# SnifferRS232.net
KiCad netlist of a schematic drawn in Altium Designer
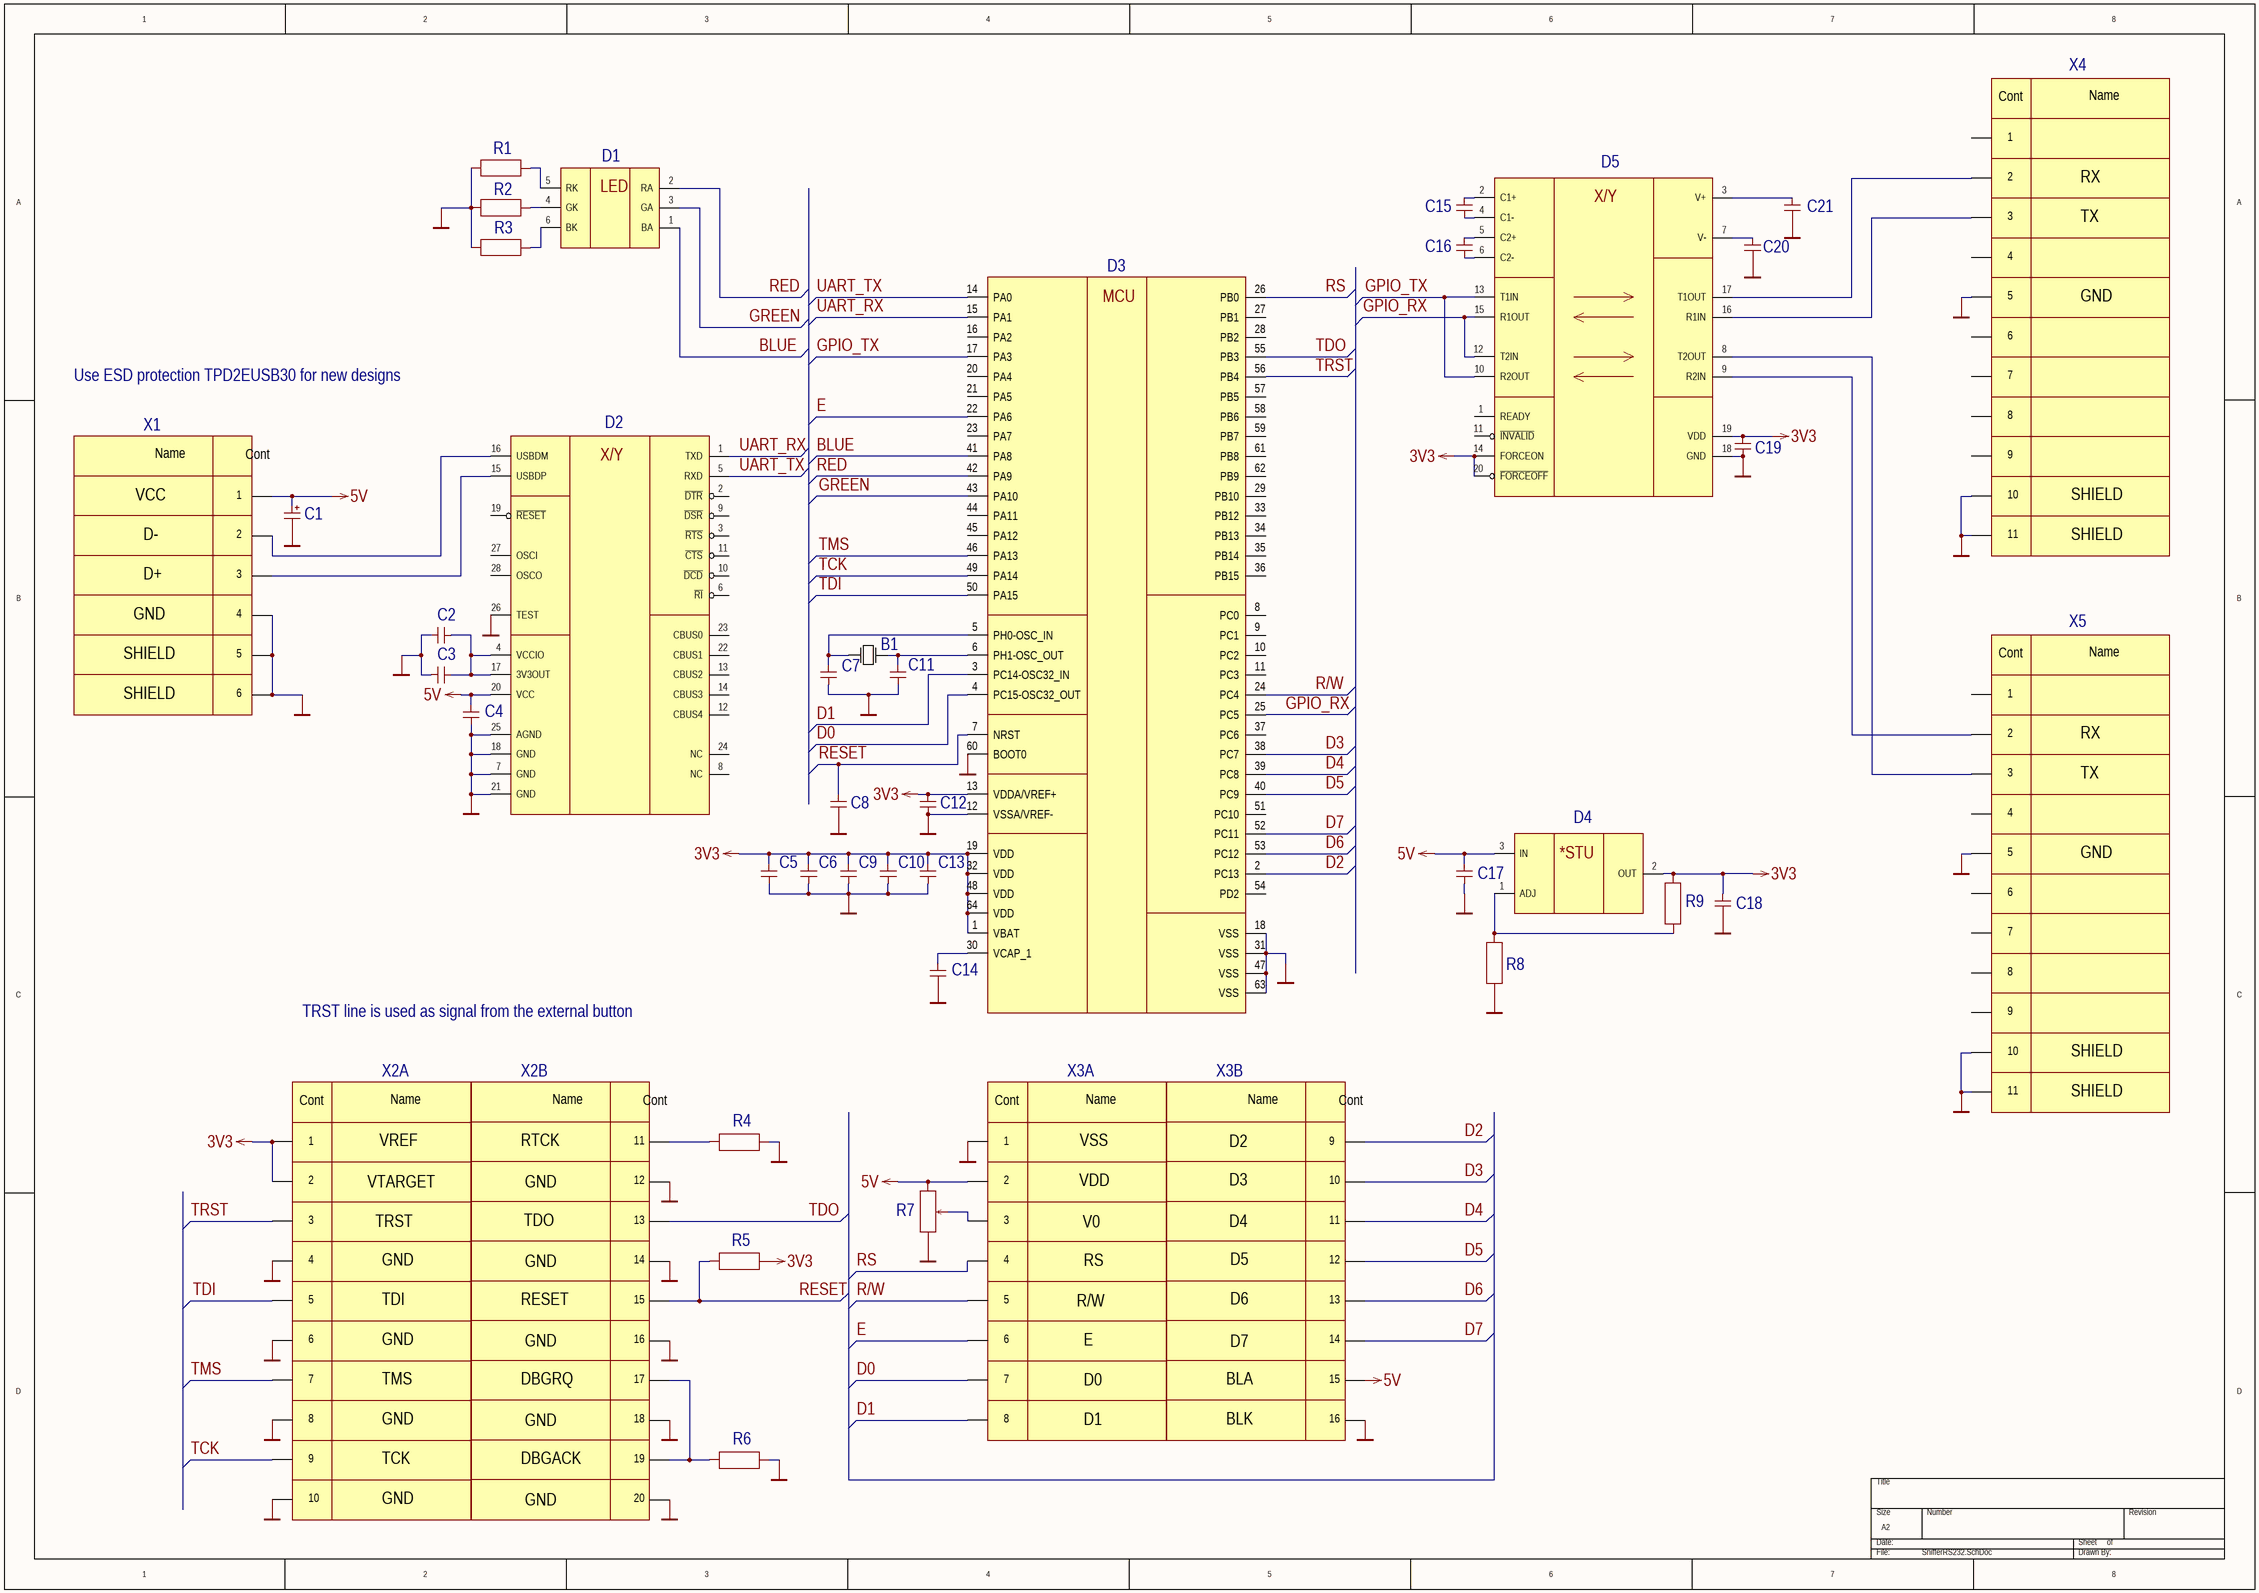
[diagram p0: SnifferRS232.SchDoc]

(export (version "E")
  (design (tool "Eeschema 10.0.6"))
  (components
    (comp (ref "B1")
      (value "ZQ1 KX-3H 25.0 MHz")
      (footprint "KX-3H")
      (description "Crystal oscillator")
      (fields (field (name "MANUFACTURER") "Geyer Electronic"))
      (libsource (lib "Devices") (part "Oscillator"))
    )
    (comp (ref "C1")
      (value "1208-16 V-100uF")
      (footprint "CAP_5x11")
      (description "Electrolytic capacitor")
      (libsource (lib "Passive,Diodes") (part "Cap_el"))
    )
    (comp (ref "C2")
      (value "0805-16 V-X7R-0.1uF±10 %")
      (footprint "SMD-0805C")
      (description "Capacitor")
      (libsource (lib "Passive,Diodes") (part "Cap"))
    )
    (comp (ref "C3")
      (value "0805-16 V-X7R-0.1uF±10 %")
      (footprint "SMD-0805C")
      (description "Capacitor")
      (libsource (lib "Passive,Diodes") (part "Cap"))
    )
    (comp (ref "C4")
      (value "0805-16 V-X7R-0.1uF±10 %")
      (footprint "SMD-0805C")
      (description "Capacitor")
      (libsource (lib "Passive,Diodes") (part "Cap"))
    )
    (comp (ref "C5")
      (value "0805-16 V-X7R-0.1uF±10 %")
      (footprint "SMD-0805C")
      (description "Capacitor")
      (libsource (lib "Passive,Diodes") (part "Cap"))
    )
    (comp (ref "C6")
      (value "0805-16 V-X7R-0.1uF±10 %")
      (footprint "SMD-0805C")
      (description "Capacitor")
      (libsource (lib "Passive,Diodes") (part "Cap"))
    )
    (comp (ref "C7")
      (value "0805-50 V-COG-22pF±5 %")
      (footprint "SMD-0805C")
      (description "Capacitor")
      (libsource (lib "Passive,Diodes") (part "Cap"))
    )
    (comp (ref "C8")
      (value "0805-16 V-X7R-0.1uF±10 %")
      (footprint "SMD-0805C")
      (description "Capacitor")
      (libsource (lib "Passive,Diodes") (part "Cap"))
    )
    (comp (ref "C9")
      (value "0805-16 V-X7R-0.1uF±10 %")
      (footprint "SMD-0805C")
      (description "Capacitor")
      (libsource (lib "Passive,Diodes") (part "Cap"))
    )
    (comp (ref "C10")
      (value "0805-16 V-X7R-0.1uF±10 %")
      (footprint "SMD-0805C")
      (description "Capacitor")
      (libsource (lib "Passive,Diodes") (part "Cap"))
    )
    (comp (ref "C11")
      (value "0805-50 V-COG-22pF±5 %")
      (footprint "SMD-0805C")
      (description "Capacitor")
      (libsource (lib "Passive,Diodes") (part "Cap"))
    )
    (comp (ref "C12")
      (value "0805-16 V-X7R-0.1uF±10 %")
      (footprint "SMD-0805C")
      (description "Capacitor")
      (libsource (lib "Passive,Diodes") (part "Cap"))
    )
    (comp (ref "C13")
      (value "0805-16 V-X7R-0.1uF±10 %")
      (footprint "SMD-0805C")
      (description "Capacitor")
      (libsource (lib "Passive,Diodes") (part "Cap"))
    )
    (comp (ref "C14")
      (value "0805-16 V-X7R-4.7uF±10 %")
      (footprint "SMD-0805C")
      (description "Capacitor")
      (libsource (lib "Passive,Diodes") (part "Cap"))
    )
    (comp (ref "C15")
      (value "0805-16 V-X7R-0.1uF±10 %")
      (footprint "SMD-0805C")
      (description "Capacitor")
      (libsource (lib "Passive,Diodes") (part "Cap"))
    )
    (comp (ref "C16")
      (value "0805-16 V-X7R-0.1uF±10 %")
      (footprint "SMD-0805C")
      (description "Capacitor")
      (libsource (lib "Passive,Diodes") (part "Cap"))
    )
    (comp (ref "C17")
      (value "0805-16 V-X7R-1uF±10 %")
      (footprint "SMD-0805C")
      (description "Capacitor")
      (libsource (lib "Passive,Diodes") (part "Cap"))
    )
    (comp (ref "C18")
      (value "0805-16 V-X7R-1uF±10 %")
      (footprint "SMD-0805C")
      (description "Capacitor")
      (libsource (lib "Passive,Diodes") (part "Cap"))
    )
    (comp (ref "C19")
      (value "0805-16 V-X7R-0.1uF±10 %")
      (footprint "SMD-0805C")
      (description "Capacitor")
      (libsource (lib "Passive,Diodes") (part "Cap"))
    )
    (comp (ref "C20")
      (value "0805-16 V-X7R-0.1uF±10 %")
      (footprint "SMD-0805C")
      (description "Capacitor")
      (libsource (lib "Passive,Diodes") (part "Cap"))
    )
    (comp (ref "C21")
      (value "0805-16 V-X7R-0.1uF±10 %")
      (footprint "SMD-0805C")
      (description "Capacitor")
      (libsource (lib "Passive,Diodes") (part "Cap"))
    )
    (comp (ref "D1")
      (value "TO-5050BC-MRPBFGF")
      (footprint "smd_50x50")
      (description "Surface mount smd LED")
      (fields (field (name "MANUFACTURER") "Oasis Technology"))
      (libsource (lib "Devices") (part "LED_RGB"))
    )
    (comp (ref "D2")
      (value "FT232RL")
      (footprint "SSOP-28_M")
      (description "USB UART Asynchronous Serial Data Transfer Chip, SSOP-28, Tape and Reel")
      (fields (field (name "MANUFACTURER") "FTDI"))
      (libsource (lib "Devices") (part "FT232R"))
    )
    (comp (ref "D3")
      (value "STM32F446RCT6")
      (footprint "LQFP64")
      (fields (field (name "MANUFACTURER") "STMicroelectronics"))
      (libsource (lib "Devices") (part "STM32F446RxT"))
    )
    (comp (ref "D4")
      (value "LM317DCYR")
      (footprint "Devices:SOT223_M")
      (description "3-Terminal Adjustable Regulator")
      (fields (field (name "MANUFACTURER") "Texas Instruments"))
      (libsource (lib "Devices") (part "LM317"))
    )
    (comp (ref "D5")
      (value "MAX3225ECAP+")
      (footprint "TSSOP-20")
      (description "±15kV ESD-Protected, 1µA, 1Mbps, 3.0V to 5.5V,  RS-232 Transceivers with AutoShutdown Plus")
      (fields (field (name "MANUFACTURER") "Maxim Integrated"))
      (libsource (lib "Devices") (part "MAX3225"))
    )
    (comp (ref "R1")
      (value "0805±5 %-680 Ohm")
      (footprint "SMD-0805-RES")
      (description "Resistor")
      (libsource (lib "Passive,Diodes") (part "Res"))
    )
    (comp (ref "R2")
      (value "0805±5 %-680 Ohm")
      (footprint "SMD-0805-RES")
      (description "Resistor")
      (libsource (lib "Passive,Diodes") (part "Res"))
    )
    (comp (ref "R3")
      (value "0805±5 %-0 Ohm")
      (footprint "SMD-0805-RES")
      (description "Resistor")
      (libsource (lib "Passive,Diodes") (part "Res"))
    )
    (comp (ref "R4")
      (value "0805±5 %-10 kOhm")
      (footprint "SMD-0805-RES")
      (description "Resistor")
      (libsource (lib "") (part "Res_1"))
    )
    (comp (ref "R5")
      (value "0805±5 %-10 kOhm")
      (footprint "SMD-0805-RES")
      (description "Resistor")
      (libsource (lib "Passive,Diodes") (part "Res"))
    )
    (comp (ref "R6")
      (value "0805±5 %-10 kOhm")
      (footprint "SMD-0805-RES")
      (description "Resistor")
      (libsource (lib "") (part "Res_1"))
    )
    (comp (ref "R7")
      (value "CA9PV10-10KA2020")
      (footprint "CA9V")
      (description "Potentiometer")
      (fields (field (name "MANUFACTURER") "ACP Technologies"))
      (libsource (lib "Passive,Diodes") (part "Potentiometer"))
    )
    (comp (ref "R8")
      (value "0805±1 %-2 kOhm")
      (footprint "SMD-0805-RES")
      (description "Resistor")
      (libsource (lib "Passive,Diodes") (part "Res"))
    )
    (comp (ref "R9")
      (value "0805±1 %-1.3 kOhm")
      (footprint "SMD-0805-RES")
      (description "Resistor")
      (libsource (lib "") (part "Res_1"))
    )
    (comp (ref "X1")
      (value "DS1099-BN0")
      (footprint "FCI USB 61729-0010BLF")
      (description "USB-B connector")
      (fields (field (name "MANUFACTURER") "Connfly Electronic"))
      (libsource (lib "Connectors") (part "USB-B"))
    )
    (comp (ref "X2")
      (value "DS1021-2*10SF11-B")
      (footprint "PLD2x10")
      (description "PLD-20 connector")
      (fields (field (name "MANUFACTURER") "Connfly Electronic"))
      (libsource (lib "Connectors") (part "PLD2x10"))
    )
    (comp (ref "X3")
      (value "DS1021-1*16SF112")
      (footprint "PLS-16_12")
      (description "PLD-16 connector")
      (fields (field (name "MANUFACTURER") "Connfly  Electronic"))
      (libsource (lib "") (part "PLD2x8_1"))
    )
    (comp (ref "X4")
      (value "DS1037-09FNAKT74-0CC")
      (footprint "DB-9F")
      (description "DB-9 female connector")
      (fields (field (name "MANUFACTURER") "Connfly Electronic"))
      (libsource (lib "Connectors") (part "DB-9"))
    )
    (comp (ref "X5")
      (value "DS1037-09MNAKT74-0CC")
      (footprint "DB-9M")
      (description "DB-9 male connector")
      (fields (field (name "MANUFACTURER") "Connfly Electronic"))
      (libsource (lib "Connectors") (part "DB-9"))
    )
  )
  (nets
    (net (code "1") (name "/BLUE") (class "Default")
      (node (ref "D1") (pin "1") (pinfunction "BA_1") (pintype "passive"))
      (node (ref "D3") (pin "41") (pinfunction "PA8_41") (pintype "passive"))
    )
    (net (code "2") (name "/D0") (class "Default")
      (node (ref "D3") (pin "4") (pinfunction "PC15-OSC32_OUT_4") (pintype "passive"))
      (node (ref "X3") (pin "7") (pinfunction "7_7") (pintype "passive"))
    )
    (net (code "3") (name "/D1") (class "Default")
      (node (ref "D3") (pin "3") (pinfunction "PC14-OSC32_IN_3") (pintype "passive"))
      (node (ref "X3") (pin "8") (pinfunction "8_8") (pintype "passive"))
    )
    (net (code "4") (name "/D2") (class "Default")
      (node (ref "D3") (pin "2") (pinfunction "PC13_2") (pintype "passive"))
      (node (ref "X3") (pin "9") (pinfunction "9_9") (pintype "passive"))
    )
    (net (code "5") (name "/D3") (class "Default")
      (node (ref "D3") (pin "38") (pinfunction "PC7_38") (pintype "passive"))
      (node (ref "X3") (pin "10") (pinfunction "10_10") (pintype "passive"))
    )
    (net (code "6") (name "/D4") (class "Default")
      (node (ref "D3") (pin "39") (pinfunction "PC8_39") (pintype "passive"))
      (node (ref "X3") (pin "11") (pinfunction "11_11") (pintype "passive"))
    )
    (net (code "7") (name "/D5") (class "Default")
      (node (ref "D3") (pin "40") (pinfunction "PC9_40") (pintype "passive"))
      (node (ref "X3") (pin "12") (pinfunction "12_12") (pintype "passive"))
    )
    (net (code "8") (name "/D6") (class "Default")
      (node (ref "D3") (pin "53") (pinfunction "PC12_53") (pintype "passive"))
      (node (ref "X3") (pin "13") (pinfunction "13_13") (pintype "passive"))
    )
    (net (code "9") (name "/D7") (class "Default")
      (node (ref "D3") (pin "52") (pinfunction "PC11_52") (pintype "passive"))
      (node (ref "X3") (pin "14") (pinfunction "14_14") (pintype "passive"))
    )
    (net (code "10") (name "/E") (class "Default")
      (node (ref "D3") (pin "22") (pinfunction "PA6_22") (pintype "passive"))
      (node (ref "X3") (pin "6") (pinfunction "6_6") (pintype "passive"))
    )
    (net (code "11") (name "/GPIO_RX") (class "Default")
      (node (ref "D3") (pin "25") (pinfunction "PC5_25") (pintype "passive"))
      (node (ref "D5") (pin "12") (pinfunction "T2IN_12") (pintype "passive"))
      (node (ref "D5") (pin "15") (pinfunction "R1OUT_15") (pintype "passive"))
    )
    (net (code "12") (name "/GPIO_TX") (class "Default")
      (node (ref "D3") (pin "17") (pinfunction "PA3_17") (pintype "passive"))
      (node (ref "D5") (pin "10") (pinfunction "R2OUT_10") (pintype "passive"))
      (node (ref "D5") (pin "13") (pinfunction "T1IN_13") (pintype "passive"))
    )
    (net (code "13") (name "/GREEN") (class "Default")
      (node (ref "D1") (pin "3") (pinfunction "GA_3") (pintype "passive"))
      (node (ref "D3") (pin "43") (pinfunction "PA10_43") (pintype "passive"))
    )
    (net (code "14") (name "/RED") (class "Default")
      (node (ref "D1") (pin "2") (pinfunction "RA_2") (pintype "passive"))
      (node (ref "D3") (pin "42") (pinfunction "PA9_42") (pintype "passive"))
    )
    (net (code "15") (name "/RESET") (class "Default")
      (node (ref "C8") (pin "1") (pinfunction "1_1") (pintype "passive"))
      (node (ref "D3") (pin "7") (pinfunction "NRST_7") (pintype "passive"))
      (node (ref "R5") (pin "2") (pinfunction "2_2") (pintype "passive"))
      (node (ref "X2") (pin "15") (pinfunction "15_15") (pintype "passive"))
    )
    (net (code "16") (name "/RS") (class "Default")
      (node (ref "D3") (pin "26") (pinfunction "PB0_26") (pintype "passive"))
      (node (ref "X3") (pin "4") (pinfunction "4_4") (pintype "passive"))
    )
    (net (code "17") (name "/R{slash}W") (class "Default")
      (node (ref "D3") (pin "24") (pinfunction "PC4_24") (pintype "passive"))
      (node (ref "X3") (pin "5") (pinfunction "5_5") (pintype "passive"))
    )
    (net (code "18") (name "/TCK") (class "Default")
      (node (ref "D3") (pin "49") (pinfunction "PA14_49") (pintype "passive"))
      (node (ref "X2") (pin "9") (pinfunction "9_9") (pintype "passive"))
    )
    (net (code "19") (name "/TDI") (class "Default")
      (node (ref "D3") (pin "50") (pinfunction "PA15_50") (pintype "passive"))
      (node (ref "X2") (pin "5") (pinfunction "5_5") (pintype "passive"))
    )
    (net (code "20") (name "/TDO") (class "Default")
      (node (ref "D3") (pin "55") (pinfunction "PB3_55") (pintype "passive"))
      (node (ref "X2") (pin "13") (pinfunction "13_13") (pintype "passive"))
    )
    (net (code "21") (name "/TMS") (class "Default")
      (node (ref "D3") (pin "46") (pinfunction "PA13_46") (pintype "passive"))
      (node (ref "X2") (pin "7") (pinfunction "7_7") (pintype "passive"))
    )
    (net (code "22") (name "/TRST") (class "Default")
      (node (ref "D3") (pin "56") (pinfunction "PB4_56") (pintype "passive"))
      (node (ref "X2") (pin "3") (pinfunction "3_3") (pintype "passive"))
    )
    (net (code "23") (name "/UART_RX") (class "Default")
      (node (ref "D2") (pin "1") (pinfunction "TXD_1") (pintype "passive"))
      (node (ref "D3") (pin "15") (pinfunction "PA1_15") (pintype "passive"))
    )
    (net (code "24") (name "/UART_TX") (class "Default")
      (node (ref "D2") (pin "5") (pinfunction "RXD_5") (pintype "passive"))
      (node (ref "D3") (pin "14") (pinfunction "PA0_14") (pintype "passive"))
    )
    (net (code "25") (name "3V3") (class "Default")
      (node (ref "C10") (pin "1") (pinfunction "1_1") (pintype "passive"))
      (node (ref "C12") (pin "1") (pinfunction "1_1") (pintype "passive"))
      (node (ref "C13") (pin "1") (pinfunction "1_1") (pintype "passive"))
      (node (ref "C18") (pin "2") (pinfunction "2_2") (pintype "passive"))
      (node (ref "C19") (pin "1") (pinfunction "1_1") (pintype "passive"))
      (node (ref "C5") (pin "1") (pinfunction "1_1") (pintype "passive"))
      (node (ref "C6") (pin "1") (pinfunction "1_1") (pintype "passive"))
      (node (ref "C9") (pin "1") (pinfunction "1_1") (pintype "passive"))
      (node (ref "D3") (pin "1") (pinfunction "VBAT_1") (pintype "power_in"))
      (node (ref "D3") (pin "13") (pinfunction "VDDA/VREF+_13") (pintype "power_in"))
      (node (ref "D3") (pin "19") (pinfunction "VDD_19") (pintype "power_in"))
      (node (ref "D3") (pin "32") (pinfunction "VDD_32") (pintype "power_in"))
      (node (ref "D3") (pin "48") (pinfunction "VDD_48") (pintype "power_in"))
      (node (ref "D3") (pin "64") (pinfunction "VDD_64") (pintype "power_in"))
      (node (ref "D4") (pin "2") (pinfunction "OUT_2") (pintype "power_in"))
      (node (ref "D5") (pin "14") (pinfunction "FORCEON_14") (pintype "passive"))
      (node (ref "D5") (pin "19") (pinfunction "VDD_19") (pintype "power_in"))
      (node (ref "D5") (pin "20") (pinfunction "~{FORCEOFF}_20") (pintype "passive"))
      (node (ref "R5") (pin "1") (pinfunction "1_1") (pintype "passive"))
      (node (ref "R9") (pin "2") (pinfunction "2_2") (pintype "passive"))
      (node (ref "X2") (pin "1") (pinfunction "1_1") (pintype "passive"))
      (node (ref "X2") (pin "2") (pinfunction "2_2") (pintype "passive"))
    )
    (net (code "26") (name "5V") (class "Default")
      (node (ref "C1") (pin "1") (pinfunction "1_1") (pintype "passive"))
      (node (ref "C17") (pin "2") (pinfunction "2_2") (pintype "passive"))
      (node (ref "C4") (pin "1") (pinfunction "1_1") (pintype "passive"))
      (node (ref "D2") (pin "20") (pinfunction "VCC_20") (pintype "power_in"))
      (node (ref "D4") (pin "3") (pinfunction "IN_3") (pintype "power_in"))
      (node (ref "R7") (pin "3") (pinfunction "3_3") (pintype "passive"))
      (node (ref "X1") (pin "1") (pinfunction "1_1") (pintype "passive"))
      (node (ref "X3") (pin "15") (pinfunction "15_15") (pintype "passive"))
      (node (ref "X3") (pin "2") (pinfunction "2_2") (pintype "passive"))
    )
    (net (code "27") (name "GND") (class "Default")
      (node (ref "C1") (pin "2") (pinfunction "2_2") (pintype "passive"))
      (node (ref "C10") (pin "2") (pinfunction "2_2") (pintype "passive"))
      (node (ref "C11") (pin "2") (pinfunction "2_2") (pintype "passive"))
      (node (ref "C12") (pin "2") (pinfunction "2_2") (pintype "passive"))
      (node (ref "C13") (pin "2") (pinfunction "2_2") (pintype "passive"))
      (node (ref "C14") (pin "2") (pinfunction "2_2") (pintype "passive"))
      (node (ref "C17") (pin "1") (pinfunction "1_1") (pintype "passive"))
      (node (ref "C18") (pin "1") (pinfunction "1_1") (pintype "passive"))
      (node (ref "C19") (pin "2") (pinfunction "2_2") (pintype "passive"))
      (node (ref "C2") (pin "1") (pinfunction "1_1") (pintype "passive"))
      (node (ref "C20") (pin "2") (pinfunction "2_2") (pintype "passive"))
      (node (ref "C21") (pin "2") (pinfunction "2_2") (pintype "passive"))
      (node (ref "C3") (pin "1") (pinfunction "1_1") (pintype "passive"))
      (node (ref "C4") (pin "2") (pinfunction "2_2") (pintype "passive"))
      (node (ref "C5") (pin "2") (pinfunction "2_2") (pintype "passive"))
      (node (ref "C6") (pin "2") (pinfunction "2_2") (pintype "passive"))
      (node (ref "C7") (pin "2") (pinfunction "2_2") (pintype "passive"))
      (node (ref "C8") (pin "2") (pinfunction "2_2") (pintype "passive"))
      (node (ref "C9") (pin "2") (pinfunction "2_2") (pintype "passive"))
      (node (ref "D2") (pin "18") (pinfunction "GND_18") (pintype "power_in"))
      (node (ref "D2") (pin "21") (pinfunction "GND_21") (pintype "power_in"))
      (node (ref "D2") (pin "25") (pinfunction "AGND_25") (pintype "power_in"))
      (node (ref "D2") (pin "26") (pinfunction "TEST_26") (pintype "passive"))
      (node (ref "D2") (pin "7") (pinfunction "GND_7") (pintype "power_in"))
      (node (ref "D3") (pin "12") (pinfunction "VSSA/VREF-_12") (pintype "power_in"))
      (node (ref "D3") (pin "18") (pinfunction "VSS_18") (pintype "power_in"))
      (node (ref "D3") (pin "31") (pinfunction "VSS_31") (pintype "power_in"))
      (node (ref "D3") (pin "47") (pinfunction "VSS_47") (pintype "power_in"))
      (node (ref "D3") (pin "60") (pinfunction "BOOT0_60") (pintype "passive"))
      (node (ref "D3") (pin "63") (pinfunction "VSS_63") (pintype "power_in"))
      (node (ref "D5") (pin "18") (pinfunction "GND_18") (pintype "power_in"))
      (node (ref "R1") (pin "2") (pinfunction "2_2") (pintype "passive"))
      (node (ref "R2") (pin "2") (pinfunction "2_2") (pintype "passive"))
      (node (ref "R3") (pin "2") (pinfunction "2_2") (pintype "passive"))
      (node (ref "R4") (pin "2") (pinfunction "2_2") (pintype "passive"))
      (node (ref "R6") (pin "2") (pinfunction "2_2") (pintype "passive"))
      (node (ref "R7") (pin "1") (pinfunction "1_1") (pintype "passive"))
      (node (ref "R8") (pin "2") (pinfunction "2_2") (pintype "passive"))
      (node (ref "X1") (pin "4") (pinfunction "4_4") (pintype "passive"))
      (node (ref "X1") (pin "5") (pinfunction "5_5") (pintype "passive"))
      (node (ref "X1") (pin "6") (pinfunction "6_6") (pintype "passive"))
      (node (ref "X2") (pin "10") (pinfunction "10_10") (pintype "passive"))
      (node (ref "X2") (pin "12") (pinfunction "12_12") (pintype "passive"))
      (node (ref "X2") (pin "14") (pinfunction "14_14") (pintype "passive"))
      (node (ref "X2") (pin "16") (pinfunction "16_16") (pintype "passive"))
      (node (ref "X2") (pin "18") (pinfunction "18_18") (pintype "passive"))
      (node (ref "X2") (pin "20") (pinfunction "20_20") (pintype "passive"))
      (node (ref "X2") (pin "4") (pinfunction "4_4") (pintype "passive"))
      (node (ref "X2") (pin "6") (pinfunction "6_6") (pintype "passive"))
      (node (ref "X2") (pin "8") (pinfunction "8_8") (pintype "passive"))
      (node (ref "X3") (pin "1") (pinfunction "1_1") (pintype "passive"))
      (node (ref "X3") (pin "16") (pinfunction "16_16") (pintype "passive"))
      (node (ref "X4") (pin "10") (pinfunction "10_10") (pintype "passive"))
      (node (ref "X4") (pin "11") (pinfunction "11_11") (pintype "passive"))
      (node (ref "X4") (pin "5") (pinfunction "5_5") (pintype "passive"))
      (node (ref "X5") (pin "10") (pinfunction "10_10") (pintype "passive"))
      (node (ref "X5") (pin "11") (pinfunction "11_11") (pintype "passive"))
      (node (ref "X5") (pin "5") (pinfunction "5_5") (pintype "passive"))
    )
    (net (code "28") (name "Net-(B1-OSCIN)") (class "Default")
      (node (ref "B1") (pin "1") (pinfunction "OSCIN_1") (pintype "passive"))
      (node (ref "C11") (pin "1") (pinfunction "1_1") (pintype "passive"))
      (node (ref "D3") (pin "6") (pinfunction "PH1-OSC_OUT_6") (pintype "passive"))
    )
    (net (code "29") (name "Net-(B1-OSCOUT)") (class "Default")
      (node (ref "B1") (pin "2") (pinfunction "OSCOUT_2") (pintype "passive"))
      (node (ref "C7") (pin "1") (pinfunction "1_1") (pintype "passive"))
      (node (ref "D3") (pin "5") (pinfunction "PH0-OSC_IN_5") (pintype "passive"))
    )
    (net (code "30") (name "Net-(D1-BK)") (class "Default")
      (node (ref "D1") (pin "6") (pinfunction "BK_6") (pintype "passive"))
      (node (ref "R3") (pin "1") (pinfunction "1_1") (pintype "passive"))
    )
    (net (code "31") (name "Net-(D1-GK)") (class "Default")
      (node (ref "D1") (pin "4") (pinfunction "GK_4") (pintype "passive"))
      (node (ref "R2") (pin "1") (pinfunction "1_1") (pintype "passive"))
    )
    (net (code "32") (name "Net-(D1-RK)") (class "Default")
      (node (ref "D1") (pin "5") (pinfunction "RK_5") (pintype "passive"))
      (node (ref "R1") (pin "1") (pinfunction "1_1") (pintype "passive"))
    )
    (net (code "33") (name "Net-(D2-3V3OUT)") (class "Default")
      (node (ref "C2") (pin "2") (pinfunction "2_2") (pintype "passive"))
      (node (ref "C3") (pin "2") (pinfunction "2_2") (pintype "passive"))
      (node (ref "D2") (pin "17") (pinfunction "3V3OUT_17") (pintype "power_in"))
      (node (ref "D2") (pin "4") (pinfunction "VCCIO_4") (pintype "power_in"))
    )
    (net (code "34") (name "Net-(D2-USBDM)") (class "Default")
      (node (ref "D2") (pin "16") (pinfunction "USBDM_16") (pintype "passive"))
      (node (ref "X1") (pin "2") (pinfunction "2_2") (pintype "passive"))
    )
    (net (code "35") (name "Net-(D2-USBDP)") (class "Default")
      (node (ref "D2") (pin "15") (pinfunction "USBDP_15") (pintype "passive"))
      (node (ref "X1") (pin "3") (pinfunction "3_3") (pintype "passive"))
    )
    (net (code "36") (name "Net-(D3-VCAP_1)") (class "Default")
      (node (ref "C14") (pin "1") (pinfunction "1_1") (pintype "passive"))
      (node (ref "D3") (pin "30") (pinfunction "VCAP_1_30") (pintype "passive"))
    )
    (net (code "37") (name "Net-(D4-ADJ)") (class "Default")
      (node (ref "D4") (pin "1") (pinfunction "ADJ_1") (pintype "passive"))
      (node (ref "R8") (pin "1") (pinfunction "1_1") (pintype "passive"))
      (node (ref "R9") (pin "1") (pinfunction "1_1") (pintype "passive"))
    )
    (net (code "38") (name "Net-(D5-C1+)") (class "Default")
      (node (ref "C15") (pin "1") (pinfunction "1_1") (pintype "passive"))
      (node (ref "D5") (pin "2") (pinfunction "C1+_2") (pintype "passive"))
    )
    (net (code "39") (name "Net-(D5-C1-)") (class "Default")
      (node (ref "C15") (pin "2") (pinfunction "2_2") (pintype "passive"))
      (node (ref "D5") (pin "4") (pinfunction "C1-_4") (pintype "passive"))
    )
    (net (code "40") (name "Net-(D5-C2+)") (class "Default")
      (node (ref "C16") (pin "1") (pinfunction "1_1") (pintype "passive"))
      (node (ref "D5") (pin "5") (pinfunction "C2+_5") (pintype "passive"))
    )
    (net (code "41") (name "Net-(D5-C2-)") (class "Default")
      (node (ref "C16") (pin "2") (pinfunction "2_2") (pintype "passive"))
      (node (ref "D5") (pin "6") (pinfunction "C2-_6") (pintype "passive"))
    )
    (net (code "42") (name "Net-(D5-R1IN)") (class "Default")
      (node (ref "D5") (pin "16") (pinfunction "R1IN_16") (pintype "passive"))
      (node (ref "X4") (pin "3") (pinfunction "3_3") (pintype "passive"))
    )
    (net (code "43") (name "Net-(D5-R2IN)") (class "Default")
      (node (ref "D5") (pin "9") (pinfunction "R2IN_9") (pintype "passive"))
      (node (ref "X5") (pin "2") (pinfunction "2_2") (pintype "passive"))
    )
    (net (code "44") (name "Net-(D5-T1OUT)") (class "Default")
      (node (ref "D5") (pin "17") (pinfunction "T1OUT_17") (pintype "passive"))
      (node (ref "X4") (pin "2") (pinfunction "2_2") (pintype "passive"))
    )
    (net (code "45") (name "Net-(D5-T2OUT)") (class "Default")
      (node (ref "D5") (pin "8") (pinfunction "T2OUT_8") (pintype "passive"))
      (node (ref "X5") (pin "3") (pinfunction "3_3") (pintype "passive"))
    )
    (net (code "46") (name "Net-(D5-V+)") (class "Default")
      (node (ref "C21") (pin "1") (pinfunction "1_1") (pintype "passive"))
      (node (ref "D5") (pin "3") (pinfunction "V+_3") (pintype "power_in"))
    )
    (net (code "47") (name "Net-(D5-V-)") (class "Default")
      (node (ref "C20") (pin "1") (pinfunction "1_1") (pintype "passive"))
      (node (ref "D5") (pin "7") (pinfunction "V-_7") (pintype "power_in"))
    )
    (net (code "48") (name "Net-(R4-Pad1)") (class "Default")
      (node (ref "R4") (pin "1") (pinfunction "1_1") (pintype "passive"))
      (node (ref "X2") (pin "11") (pinfunction "11_11") (pintype "passive"))
    )
    (net (code "49") (name "Net-(R6-Pad1)") (class "Default")
      (node (ref "R6") (pin "1") (pinfunction "1_1") (pintype "passive"))
      (node (ref "X2") (pin "17") (pinfunction "17_17") (pintype "passive"))
      (node (ref "X2") (pin "19") (pinfunction "19_19") (pintype "passive"))
    )
    (net (code "50") (name "Net-(R7-Pad2)") (class "Default")
      (node (ref "R7") (pin "2") (pinfunction "2_2") (pintype "passive"))
      (node (ref "X3") (pin "3") (pinfunction "3_3") (pintype "passive"))
    )
    (net (code "51") (name "unconnected-(D2-CBUS0-Pad23)") (class "Default")
      (node (ref "D2") (pin "23") (pinfunction "CBUS0_23") (pintype "passive"))
    )
    (net (code "52") (name "unconnected-(D2-CBUS1-Pad22)") (class "Default")
      (node (ref "D2") (pin "22") (pinfunction "CBUS1_22") (pintype "passive"))
    )
    (net (code "53") (name "unconnected-(D2-CBUS2-Pad13)") (class "Default")
      (node (ref "D2") (pin "13") (pinfunction "CBUS2_13") (pintype "passive"))
    )
    (net (code "54") (name "unconnected-(D2-CBUS3-Pad14)") (class "Default")
      (node (ref "D2") (pin "14") (pinfunction "CBUS3_14") (pintype "passive"))
    )
    (net (code "55") (name "unconnected-(D2-CBUS4-Pad12)") (class "Default")
      (node (ref "D2") (pin "12") (pinfunction "CBUS4_12") (pintype "passive"))
    )
    (net (code "56") (name "unconnected-(D2-NC-Pad8)") (class "Default")
      (node (ref "D2") (pin "8") (pinfunction "NC_8") (pintype "passive"))
    )
    (net (code "57") (name "unconnected-(D2-NC-Pad24)") (class "Default")
      (node (ref "D2") (pin "24") (pinfunction "NC_24") (pintype "passive"))
    )
    (net (code "58") (name "unconnected-(D2-OSCI-Pad27)") (class "Default")
      (node (ref "D2") (pin "27") (pinfunction "OSCI_27") (pintype "passive"))
    )
    (net (code "59") (name "unconnected-(D2-OSCO-Pad28)") (class "Default")
      (node (ref "D2") (pin "28") (pinfunction "OSCO_28") (pintype "passive"))
    )
    (net (code "60") (name "unconnected-(D2-~{CTS}-Pad11)") (class "Default")
      (node (ref "D2") (pin "11") (pinfunction "~{CTS}_11") (pintype "passive"))
    )
    (net (code "61") (name "unconnected-(D2-~{DCD}-Pad10)") (class "Default")
      (node (ref "D2") (pin "10") (pinfunction "~{DCD}_10") (pintype "passive"))
    )
    (net (code "62") (name "unconnected-(D2-~{DSR}-Pad9)") (class "Default")
      (node (ref "D2") (pin "9") (pinfunction "~{DSR}_9") (pintype "passive"))
    )
    (net (code "63") (name "unconnected-(D2-~{DTR}-Pad2)") (class "Default")
      (node (ref "D2") (pin "2") (pinfunction "~{DTR}_2") (pintype "passive"))
    )
    (net (code "64") (name "unconnected-(D2-~{RESET}-Pad19)") (class "Default")
      (node (ref "D2") (pin "19") (pinfunction "~{RESET}_19") (pintype "passive"))
    )
    (net (code "65") (name "unconnected-(D2-~{RI}-Pad6)") (class "Default")
      (node (ref "D2") (pin "6") (pinfunction "~{RI}_6") (pintype "passive"))
    )
    (net (code "66") (name "unconnected-(D2-~{RTS}-Pad3)") (class "Default")
      (node (ref "D2") (pin "3") (pinfunction "~{RTS}_3") (pintype "passive"))
    )
    (net (code "67") (name "unconnected-(D3-PA2-Pad16)") (class "Default")
      (node (ref "D3") (pin "16") (pinfunction "PA2_16") (pintype "passive"))
    )
    (net (code "68") (name "unconnected-(D3-PA4-Pad20)") (class "Default")
      (node (ref "D3") (pin "20") (pinfunction "PA4_20") (pintype "passive"))
    )
    (net (code "69") (name "unconnected-(D3-PA5-Pad21)") (class "Default")
      (node (ref "D3") (pin "21") (pinfunction "PA5_21") (pintype "passive"))
    )
    (net (code "70") (name "unconnected-(D3-PA7-Pad23)") (class "Default")
      (node (ref "D3") (pin "23") (pinfunction "PA7_23") (pintype "passive"))
    )
    (net (code "71") (name "unconnected-(D3-PA11-Pad44)") (class "Default")
      (node (ref "D3") (pin "44") (pinfunction "PA11_44") (pintype "passive"))
    )
    (net (code "72") (name "unconnected-(D3-PA12-Pad45)") (class "Default")
      (node (ref "D3") (pin "45") (pinfunction "PA12_45") (pintype "passive"))
    )
    (net (code "73") (name "unconnected-(D3-PB1-Pad27)") (class "Default")
      (node (ref "D3") (pin "27") (pinfunction "PB1_27") (pintype "passive"))
    )
    (net (code "74") (name "unconnected-(D3-PB2-Pad28)") (class "Default")
      (node (ref "D3") (pin "28") (pinfunction "PB2_28") (pintype "passive"))
    )
    (net (code "75") (name "unconnected-(D3-PB5-Pad57)") (class "Default")
      (node (ref "D3") (pin "57") (pinfunction "PB5_57") (pintype "passive"))
    )
    (net (code "76") (name "unconnected-(D3-PB6-Pad58)") (class "Default")
      (node (ref "D3") (pin "58") (pinfunction "PB6_58") (pintype "passive"))
    )
    (net (code "77") (name "unconnected-(D3-PB7-Pad59)") (class "Default")
      (node (ref "D3") (pin "59") (pinfunction "PB7_59") (pintype "passive"))
    )
    (net (code "78") (name "unconnected-(D3-PB8-Pad61)") (class "Default")
      (node (ref "D3") (pin "61") (pinfunction "PB8_61") (pintype "passive"))
    )
    (net (code "79") (name "unconnected-(D3-PB9-Pad62)") (class "Default")
      (node (ref "D3") (pin "62") (pinfunction "PB9_62") (pintype "passive"))
    )
    (net (code "80") (name "unconnected-(D3-PB10-Pad29)") (class "Default")
      (node (ref "D3") (pin "29") (pinfunction "PB10_29") (pintype "passive"))
    )
    (net (code "81") (name "unconnected-(D3-PB12-Pad33)") (class "Default")
      (node (ref "D3") (pin "33") (pinfunction "PB12_33") (pintype "passive"))
    )
    (net (code "82") (name "unconnected-(D3-PB13-Pad34)") (class "Default")
      (node (ref "D3") (pin "34") (pinfunction "PB13_34") (pintype "passive"))
    )
    (net (code "83") (name "unconnected-(D3-PB14-Pad35)") (class "Default")
      (node (ref "D3") (pin "35") (pinfunction "PB14_35") (pintype "passive"))
    )
    (net (code "84") (name "unconnected-(D3-PB15-Pad36)") (class "Default")
      (node (ref "D3") (pin "36") (pinfunction "PB15_36") (pintype "passive"))
    )
    (net (code "85") (name "unconnected-(D3-PC0-Pad8)") (class "Default")
      (node (ref "D3") (pin "8") (pinfunction "PC0_8") (pintype "passive"))
    )
    (net (code "86") (name "unconnected-(D3-PC1-Pad9)") (class "Default")
      (node (ref "D3") (pin "9") (pinfunction "PC1_9") (pintype "passive"))
    )
    (net (code "87") (name "unconnected-(D3-PC2-Pad10)") (class "Default")
      (node (ref "D3") (pin "10") (pinfunction "PC2_10") (pintype "passive"))
    )
    (net (code "88") (name "unconnected-(D3-PC3-Pad11)") (class "Default")
      (node (ref "D3") (pin "11") (pinfunction "PC3_11") (pintype "passive"))
    )
    (net (code "89") (name "unconnected-(D3-PC6-Pad37)") (class "Default")
      (node (ref "D3") (pin "37") (pinfunction "PC6_37") (pintype "passive"))
    )
    (net (code "90") (name "unconnected-(D3-PC10-Pad51)") (class "Default")
      (node (ref "D3") (pin "51") (pinfunction "PC10_51") (pintype "passive"))
    )
    (net (code "91") (name "unconnected-(D3-PD2-Pad54)") (class "Default")
      (node (ref "D3") (pin "54") (pinfunction "PD2_54") (pintype "passive"))
    )
    (net (code "92") (name "unconnected-(D5-READY-Pad1)") (class "Default")
      (node (ref "D5") (pin "1") (pinfunction "READY_1") (pintype "passive"))
    )
    (net (code "93") (name "unconnected-(D5-~{INVALID}-Pad11)") (class "Default")
      (node (ref "D5") (pin "11") (pinfunction "~{INVALID}_11") (pintype "passive"))
    )
    (net (code "94") (name "unconnected-(X4-Pad1)") (class "Default")
      (node (ref "X4") (pin "1") (pinfunction "1_1") (pintype "passive"))
    )
    (net (code "95") (name "unconnected-(X4-Pad4)") (class "Default")
      (node (ref "X4") (pin "4") (pinfunction "4_4") (pintype "passive"))
    )
    (net (code "96") (name "unconnected-(X4-Pad6)") (class "Default")
      (node (ref "X4") (pin "6") (pinfunction "6_6") (pintype "passive"))
    )
    (net (code "97") (name "unconnected-(X4-Pad7)") (class "Default")
      (node (ref "X4") (pin "7") (pinfunction "7_7") (pintype "passive"))
    )
    (net (code "98") (name "unconnected-(X4-Pad8)") (class "Default")
      (node (ref "X4") (pin "8") (pinfunction "8_8") (pintype "passive"))
    )
    (net (code "99") (name "unconnected-(X4-Pad9)") (class "Default")
      (node (ref "X4") (pin "9") (pinfunction "9_9") (pintype "passive"))
    )
    (net (code "100") (name "unconnected-(X5-Pad1)") (class "Default")
      (node (ref "X5") (pin "1") (pinfunction "1_1") (pintype "passive"))
    )
    (net (code "101") (name "unconnected-(X5-Pad4)") (class "Default")
      (node (ref "X5") (pin "4") (pinfunction "4_4") (pintype "passive"))
    )
    (net (code "102") (name "unconnected-(X5-Pad6)") (class "Default")
      (node (ref "X5") (pin "6") (pinfunction "6_6") (pintype "passive"))
    )
    (net (code "103") (name "unconnected-(X5-Pad7)") (class "Default")
      (node (ref "X5") (pin "7") (pinfunction "7_7") (pintype "passive"))
    )
    (net (code "104") (name "unconnected-(X5-Pad8)") (class "Default")
      (node (ref "X5") (pin "8") (pinfunction "8_8") (pintype "passive"))
    )
    (net (code "105") (name "unconnected-(X5-Pad9)") (class "Default")
      (node (ref "X5") (pin "9") (pinfunction "9_9") (pintype "passive"))
    )
  )
)
